# midicontroller.net
KiCad netlist of a schematic drawn in EAGLE
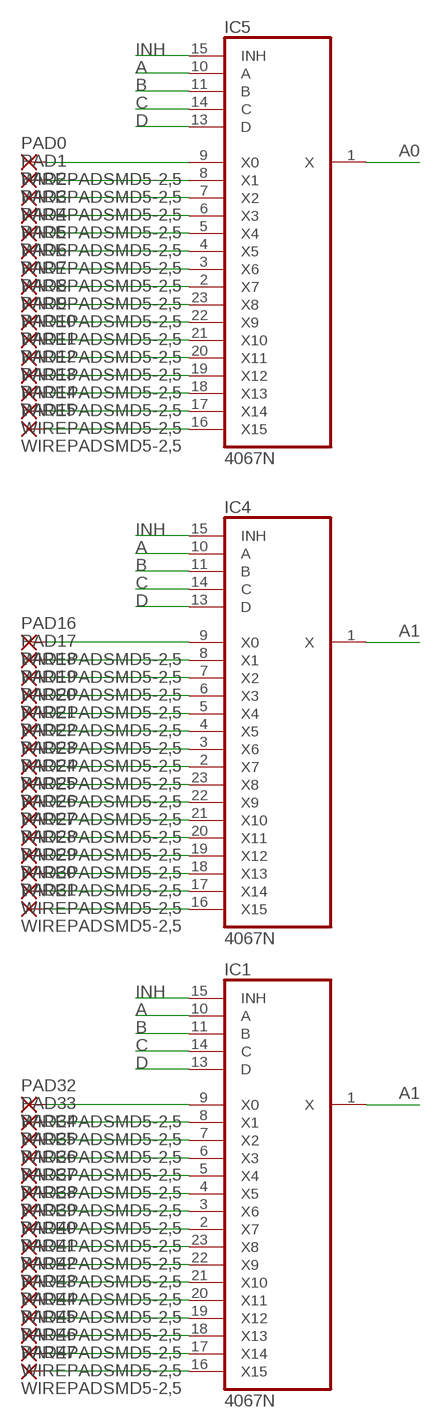
[diagram p0: schematic, sheet 1]

(export (version "E")
  (design (tool "Eeschema 10.0.6"))
  (components
    (comp (ref "IC1")
      (value "4067N")
      (footprint "eagle-import:DIL24-6")
      (libsource (lib "eagle-import") (part "4067N"))
    )
    (comp (ref "IC4")
      (value "4067N")
      (footprint "eagle-import:DIL24-6")
      (libsource (lib "eagle-import") (part "4067N"))
    )
    (comp (ref "IC5")
      (value "4067N")
      (footprint "eagle-import:DIL24-6")
      (libsource (lib "eagle-import") (part "4067N"))
    )
    (comp (ref "PAD0")
      (value "WIREPADSMD5-2,5")
      (footprint "eagle-import:5-2,5")
      (libsource (lib "eagle-import") (part "WIREPADSMD5-2,5"))
    )
    (comp (ref "PAD1")
      (value "WIREPADSMD5-2,5")
      (footprint "eagle-import:5-2,5")
      (libsource (lib "eagle-import") (part "WIREPADSMD5-2,5"))
    )
    (comp (ref "PAD2")
      (value "WIREPADSMD5-2,5")
      (footprint "eagle-import:5-2,5")
      (libsource (lib "eagle-import") (part "WIREPADSMD5-2,5"))
    )
    (comp (ref "PAD3")
      (value "WIREPADSMD5-2,5")
      (footprint "eagle-import:5-2,5")
      (libsource (lib "eagle-import") (part "WIREPADSMD5-2,5"))
    )
    (comp (ref "PAD4")
      (value "WIREPADSMD5-2,5")
      (footprint "eagle-import:5-2,5")
      (libsource (lib "eagle-import") (part "WIREPADSMD5-2,5"))
    )
    (comp (ref "PAD5")
      (value "WIREPADSMD5-2,5")
      (footprint "eagle-import:5-2,5")
      (libsource (lib "eagle-import") (part "WIREPADSMD5-2,5"))
    )
    (comp (ref "PAD6")
      (value "WIREPADSMD5-2,5")
      (footprint "eagle-import:5-2,5")
      (libsource (lib "eagle-import") (part "WIREPADSMD5-2,5"))
    )
    (comp (ref "PAD7")
      (value "WIREPADSMD5-2,5")
      (footprint "eagle-import:5-2,5")
      (libsource (lib "eagle-import") (part "WIREPADSMD5-2,5"))
    )
    (comp (ref "PAD8")
      (value "WIREPADSMD5-2,5")
      (footprint "eagle-import:5-2,5")
      (libsource (lib "eagle-import") (part "WIREPADSMD5-2,5"))
    )
    (comp (ref "PAD9")
      (value "WIREPADSMD5-2,5")
      (footprint "eagle-import:5-2,5")
      (libsource (lib "eagle-import") (part "WIREPADSMD5-2,5"))
    )
    (comp (ref "PAD10")
      (value "WIREPADSMD5-2,5")
      (footprint "eagle-import:5-2,5")
      (libsource (lib "eagle-import") (part "WIREPADSMD5-2,5"))
    )
    (comp (ref "PAD11")
      (value "WIREPADSMD5-2,5")
      (footprint "eagle-import:5-2,5")
      (libsource (lib "eagle-import") (part "WIREPADSMD5-2,5"))
    )
    (comp (ref "PAD12")
      (value "WIREPADSMD5-2,5")
      (footprint "eagle-import:5-2,5")
      (libsource (lib "eagle-import") (part "WIREPADSMD5-2,5"))
    )
    (comp (ref "PAD13")
      (value "WIREPADSMD5-2,5")
      (footprint "eagle-import:5-2,5")
      (libsource (lib "eagle-import") (part "WIREPADSMD5-2,5"))
    )
    (comp (ref "PAD14")
      (value "WIREPADSMD5-2,5")
      (footprint "eagle-import:5-2,5")
      (libsource (lib "eagle-import") (part "WIREPADSMD5-2,5"))
    )
    (comp (ref "PAD15")
      (value "WIREPADSMD5-2,5")
      (footprint "eagle-import:5-2,5")
      (libsource (lib "eagle-import") (part "WIREPADSMD5-2,5"))
    )
    (comp (ref "PAD16")
      (value "WIREPADSMD5-2,5")
      (footprint "eagle-import:5-2,5")
      (libsource (lib "eagle-import") (part "WIREPADSMD5-2,5"))
    )
    (comp (ref "PAD17")
      (value "WIREPADSMD5-2,5")
      (footprint "eagle-import:5-2,5")
      (libsource (lib "eagle-import") (part "WIREPADSMD5-2,5"))
    )
    (comp (ref "PAD18")
      (value "WIREPADSMD5-2,5")
      (footprint "eagle-import:5-2,5")
      (libsource (lib "eagle-import") (part "WIREPADSMD5-2,5"))
    )
    (comp (ref "PAD19")
      (value "WIREPADSMD5-2,5")
      (footprint "eagle-import:5-2,5")
      (libsource (lib "eagle-import") (part "WIREPADSMD5-2,5"))
    )
    (comp (ref "PAD20")
      (value "WIREPADSMD5-2,5")
      (footprint "eagle-import:5-2,5")
      (libsource (lib "eagle-import") (part "WIREPADSMD5-2,5"))
    )
    (comp (ref "PAD21")
      (value "WIREPADSMD5-2,5")
      (footprint "eagle-import:5-2,5")
      (libsource (lib "eagle-import") (part "WIREPADSMD5-2,5"))
    )
    (comp (ref "PAD22")
      (value "WIREPADSMD5-2,5")
      (footprint "eagle-import:5-2,5")
      (libsource (lib "eagle-import") (part "WIREPADSMD5-2,5"))
    )
    (comp (ref "PAD23")
      (value "WIREPADSMD5-2,5")
      (footprint "eagle-import:5-2,5")
      (libsource (lib "eagle-import") (part "WIREPADSMD5-2,5"))
    )
    (comp (ref "PAD24")
      (value "WIREPADSMD5-2,5")
      (footprint "eagle-import:5-2,5")
      (libsource (lib "eagle-import") (part "WIREPADSMD5-2,5"))
    )
    (comp (ref "PAD25")
      (value "WIREPADSMD5-2,5")
      (footprint "eagle-import:5-2,5")
      (libsource (lib "eagle-import") (part "WIREPADSMD5-2,5"))
    )
    (comp (ref "PAD26")
      (value "WIREPADSMD5-2,5")
      (footprint "eagle-import:5-2,5")
      (libsource (lib "eagle-import") (part "WIREPADSMD5-2,5"))
    )
    (comp (ref "PAD27")
      (value "WIREPADSMD5-2,5")
      (footprint "eagle-import:5-2,5")
      (libsource (lib "eagle-import") (part "WIREPADSMD5-2,5"))
    )
    (comp (ref "PAD28")
      (value "WIREPADSMD5-2,5")
      (footprint "eagle-import:5-2,5")
      (libsource (lib "eagle-import") (part "WIREPADSMD5-2,5"))
    )
    (comp (ref "PAD29")
      (value "WIREPADSMD5-2,5")
      (footprint "eagle-import:5-2,5")
      (libsource (lib "eagle-import") (part "WIREPADSMD5-2,5"))
    )
    (comp (ref "PAD30")
      (value "WIREPADSMD5-2,5")
      (footprint "eagle-import:5-2,5")
      (libsource (lib "eagle-import") (part "WIREPADSMD5-2,5"))
    )
    (comp (ref "PAD31")
      (value "WIREPADSMD5-2,5")
      (footprint "eagle-import:5-2,5")
      (libsource (lib "eagle-import") (part "WIREPADSMD5-2,5"))
    )
    (comp (ref "PAD32")
      (value "WIREPADSMD5-2,5")
      (footprint "eagle-import:5-2,5")
      (libsource (lib "eagle-import") (part "WIREPADSMD5-2,5"))
    )
    (comp (ref "PAD33")
      (value "WIREPADSMD5-2,5")
      (footprint "eagle-import:5-2,5")
      (libsource (lib "eagle-import") (part "WIREPADSMD5-2,5"))
    )
    (comp (ref "PAD34")
      (value "WIREPADSMD5-2,5")
      (footprint "eagle-import:5-2,5")
      (libsource (lib "eagle-import") (part "WIREPADSMD5-2,5"))
    )
    (comp (ref "PAD35")
      (value "WIREPADSMD5-2,5")
      (footprint "eagle-import:5-2,5")
      (libsource (lib "eagle-import") (part "WIREPADSMD5-2,5"))
    )
    (comp (ref "PAD36")
      (value "WIREPADSMD5-2,5")
      (footprint "eagle-import:5-2,5")
      (libsource (lib "eagle-import") (part "WIREPADSMD5-2,5"))
    )
    (comp (ref "PAD37")
      (value "WIREPADSMD5-2,5")
      (footprint "eagle-import:5-2,5")
      (libsource (lib "eagle-import") (part "WIREPADSMD5-2,5"))
    )
    (comp (ref "PAD38")
      (value "WIREPADSMD5-2,5")
      (footprint "eagle-import:5-2,5")
      (libsource (lib "eagle-import") (part "WIREPADSMD5-2,5"))
    )
    (comp (ref "PAD39")
      (value "WIREPADSMD5-2,5")
      (footprint "eagle-import:5-2,5")
      (libsource (lib "eagle-import") (part "WIREPADSMD5-2,5"))
    )
    (comp (ref "PAD40")
      (value "WIREPADSMD5-2,5")
      (footprint "eagle-import:5-2,5")
      (libsource (lib "eagle-import") (part "WIREPADSMD5-2,5"))
    )
    (comp (ref "PAD41")
      (value "WIREPADSMD5-2,5")
      (footprint "eagle-import:5-2,5")
      (libsource (lib "eagle-import") (part "WIREPADSMD5-2,5"))
    )
    (comp (ref "PAD42")
      (value "WIREPADSMD5-2,5")
      (footprint "eagle-import:5-2,5")
      (libsource (lib "eagle-import") (part "WIREPADSMD5-2,5"))
    )
    (comp (ref "PAD43")
      (value "WIREPADSMD5-2,5")
      (footprint "eagle-import:5-2,5")
      (libsource (lib "eagle-import") (part "WIREPADSMD5-2,5"))
    )
    (comp (ref "PAD44")
      (value "WIREPADSMD5-2,5")
      (footprint "eagle-import:5-2,5")
      (libsource (lib "eagle-import") (part "WIREPADSMD5-2,5"))
    )
    (comp (ref "PAD45")
      (value "WIREPADSMD5-2,5")
      (footprint "eagle-import:5-2,5")
      (libsource (lib "eagle-import") (part "WIREPADSMD5-2,5"))
    )
    (comp (ref "PAD46")
      (value "WIREPADSMD5-2,5")
      (footprint "eagle-import:5-2,5")
      (libsource (lib "eagle-import") (part "WIREPADSMD5-2,5"))
    )
    (comp (ref "PAD47")
      (value "WIREPADSMD5-2,5")
      (footprint "eagle-import:5-2,5")
      (libsource (lib "eagle-import") (part "WIREPADSMD5-2,5"))
    )
  )
  (nets
    (net (code "1") (name "/A") (class "Default")
      (node (ref "IC1") (pin "10") (pinfunction "A_10") (pintype "input"))
      (node (ref "IC4") (pin "10") (pinfunction "A_10") (pintype "input"))
      (node (ref "IC5") (pin "10") (pinfunction "A_10") (pintype "input"))
    )
    (net (code "2") (name "/A0") (class "Default")
      (node (ref "IC5") (pin "1") (pinfunction "X_1") (pintype "output"))
    )
    (net (code "3") (name "/A1") (class "Default")
      (node (ref "IC1") (pin "1") (pinfunction "X_1") (pintype "output"))
      (node (ref "IC4") (pin "1") (pinfunction "X_1") (pintype "output"))
    )
    (net (code "4") (name "/B") (class "Default")
      (node (ref "IC1") (pin "11") (pinfunction "B_11") (pintype "input"))
      (node (ref "IC4") (pin "11") (pinfunction "B_11") (pintype "input"))
      (node (ref "IC5") (pin "11") (pinfunction "B_11") (pintype "input"))
    )
    (net (code "5") (name "/C") (class "Default")
      (node (ref "IC1") (pin "14") (pinfunction "C_14") (pintype "input"))
      (node (ref "IC4") (pin "14") (pinfunction "C_14") (pintype "input"))
      (node (ref "IC5") (pin "14") (pinfunction "C_14") (pintype "input"))
    )
    (net (code "6") (name "/D") (class "Default")
      (node (ref "IC1") (pin "13") (pinfunction "D_13") (pintype "input"))
      (node (ref "IC4") (pin "13") (pinfunction "D_13") (pintype "input"))
      (node (ref "IC5") (pin "13") (pinfunction "D_13") (pintype "input"))
    )
    (net (code "7") (name "/INH") (class "Default")
      (node (ref "IC1") (pin "15") (pinfunction "INH_15") (pintype "input"))
      (node (ref "IC4") (pin "15") (pinfunction "INH_15") (pintype "input"))
      (node (ref "IC5") (pin "15") (pinfunction "INH_15") (pintype "input"))
    )
    (net (code "8") (name "Net-(IC1A-X0)") (class "Default")
      (node (ref "IC1") (pin "9") (pinfunction "X0_9") (pintype "input"))
      (node (ref "PAD32") (pin "1") (pinfunction "P_1") (pintype "passive"))
    )
    (net (code "9") (name "Net-(IC1A-X1)") (class "Default")
      (node (ref "IC1") (pin "8") (pinfunction "X1_8") (pintype "input"))
      (node (ref "PAD33") (pin "1") (pinfunction "P_1") (pintype "passive"))
    )
    (net (code "10") (name "Net-(IC1A-X2)") (class "Default")
      (node (ref "IC1") (pin "7") (pinfunction "X2_7") (pintype "input"))
      (node (ref "PAD34") (pin "1") (pinfunction "P_1") (pintype "passive"))
    )
    (net (code "11") (name "Net-(IC1A-X3)") (class "Default")
      (node (ref "IC1") (pin "6") (pinfunction "X3_6") (pintype "input"))
      (node (ref "PAD35") (pin "1") (pinfunction "P_1") (pintype "passive"))
    )
    (net (code "12") (name "Net-(IC1A-X4)") (class "Default")
      (node (ref "IC1") (pin "5") (pinfunction "X4_5") (pintype "input"))
      (node (ref "PAD36") (pin "1") (pinfunction "P_1") (pintype "passive"))
    )
    (net (code "13") (name "Net-(IC1A-X5)") (class "Default")
      (node (ref "IC1") (pin "4") (pinfunction "X5_4") (pintype "input"))
      (node (ref "PAD37") (pin "1") (pinfunction "P_1") (pintype "passive"))
    )
    (net (code "14") (name "Net-(IC1A-X6)") (class "Default")
      (node (ref "IC1") (pin "3") (pinfunction "X6_3") (pintype "input"))
      (node (ref "PAD38") (pin "1") (pinfunction "P_1") (pintype "passive"))
    )
    (net (code "15") (name "Net-(IC1A-X7)") (class "Default")
      (node (ref "IC1") (pin "2") (pinfunction "X7_2") (pintype "input"))
      (node (ref "PAD39") (pin "1") (pinfunction "P_1") (pintype "passive"))
    )
    (net (code "16") (name "Net-(IC1A-X8)") (class "Default")
      (node (ref "IC1") (pin "23") (pinfunction "X8_23") (pintype "input"))
      (node (ref "PAD40") (pin "1") (pinfunction "P_1") (pintype "passive"))
    )
    (net (code "17") (name "Net-(IC1A-X9)") (class "Default")
      (node (ref "IC1") (pin "22") (pinfunction "X9_22") (pintype "input"))
      (node (ref "PAD41") (pin "1") (pinfunction "P_1") (pintype "passive"))
    )
    (net (code "18") (name "Net-(IC1A-X10)") (class "Default")
      (node (ref "IC1") (pin "21") (pinfunction "X10_21") (pintype "input"))
      (node (ref "PAD42") (pin "1") (pinfunction "P_1") (pintype "passive"))
    )
    (net (code "19") (name "Net-(IC1A-X11)") (class "Default")
      (node (ref "IC1") (pin "20") (pinfunction "X11_20") (pintype "input"))
      (node (ref "PAD43") (pin "1") (pinfunction "P_1") (pintype "passive"))
    )
    (net (code "20") (name "Net-(IC1A-X12)") (class "Default")
      (node (ref "IC1") (pin "19") (pinfunction "X12_19") (pintype "input"))
      (node (ref "PAD44") (pin "1") (pinfunction "P_1") (pintype "passive"))
    )
    (net (code "21") (name "Net-(IC1A-X13)") (class "Default")
      (node (ref "IC1") (pin "18") (pinfunction "X13_18") (pintype "input"))
      (node (ref "PAD45") (pin "1") (pinfunction "P_1") (pintype "passive"))
    )
    (net (code "22") (name "Net-(IC1A-X14)") (class "Default")
      (node (ref "IC1") (pin "17") (pinfunction "X14_17") (pintype "input"))
      (node (ref "PAD46") (pin "1") (pinfunction "P_1") (pintype "passive"))
    )
    (net (code "23") (name "Net-(IC1A-X15)") (class "Default")
      (node (ref "IC1") (pin "16") (pinfunction "X15_16") (pintype "input"))
      (node (ref "PAD47") (pin "1") (pinfunction "P_1") (pintype "passive"))
    )
    (net (code "24") (name "Net-(IC4A-X0)") (class "Default")
      (node (ref "IC4") (pin "9") (pinfunction "X0_9") (pintype "input"))
      (node (ref "PAD16") (pin "1") (pinfunction "P_1") (pintype "passive"))
    )
    (net (code "25") (name "Net-(IC4A-X1)") (class "Default")
      (node (ref "IC4") (pin "8") (pinfunction "X1_8") (pintype "input"))
      (node (ref "PAD17") (pin "1") (pinfunction "P_1") (pintype "passive"))
    )
    (net (code "26") (name "Net-(IC4A-X2)") (class "Default")
      (node (ref "IC4") (pin "7") (pinfunction "X2_7") (pintype "input"))
      (node (ref "PAD18") (pin "1") (pinfunction "P_1") (pintype "passive"))
    )
    (net (code "27") (name "Net-(IC4A-X3)") (class "Default")
      (node (ref "IC4") (pin "6") (pinfunction "X3_6") (pintype "input"))
      (node (ref "PAD19") (pin "1") (pinfunction "P_1") (pintype "passive"))
    )
    (net (code "28") (name "Net-(IC4A-X4)") (class "Default")
      (node (ref "IC4") (pin "5") (pinfunction "X4_5") (pintype "input"))
      (node (ref "PAD20") (pin "1") (pinfunction "P_1") (pintype "passive"))
    )
    (net (code "29") (name "Net-(IC4A-X5)") (class "Default")
      (node (ref "IC4") (pin "4") (pinfunction "X5_4") (pintype "input"))
      (node (ref "PAD21") (pin "1") (pinfunction "P_1") (pintype "passive"))
    )
    (net (code "30") (name "Net-(IC4A-X6)") (class "Default")
      (node (ref "IC4") (pin "3") (pinfunction "X6_3") (pintype "input"))
      (node (ref "PAD22") (pin "1") (pinfunction "P_1") (pintype "passive"))
    )
    (net (code "31") (name "Net-(IC4A-X7)") (class "Default")
      (node (ref "IC4") (pin "2") (pinfunction "X7_2") (pintype "input"))
      (node (ref "PAD23") (pin "1") (pinfunction "P_1") (pintype "passive"))
    )
    (net (code "32") (name "Net-(IC4A-X8)") (class "Default")
      (node (ref "IC4") (pin "23") (pinfunction "X8_23") (pintype "input"))
      (node (ref "PAD24") (pin "1") (pinfunction "P_1") (pintype "passive"))
    )
    (net (code "33") (name "Net-(IC4A-X9)") (class "Default")
      (node (ref "IC4") (pin "22") (pinfunction "X9_22") (pintype "input"))
      (node (ref "PAD25") (pin "1") (pinfunction "P_1") (pintype "passive"))
    )
    (net (code "34") (name "Net-(IC4A-X10)") (class "Default")
      (node (ref "IC4") (pin "21") (pinfunction "X10_21") (pintype "input"))
      (node (ref "PAD26") (pin "1") (pinfunction "P_1") (pintype "passive"))
    )
    (net (code "35") (name "Net-(IC4A-X11)") (class "Default")
      (node (ref "IC4") (pin "20") (pinfunction "X11_20") (pintype "input"))
      (node (ref "PAD27") (pin "1") (pinfunction "P_1") (pintype "passive"))
    )
    (net (code "36") (name "Net-(IC4A-X12)") (class "Default")
      (node (ref "IC4") (pin "19") (pinfunction "X12_19") (pintype "input"))
      (node (ref "PAD28") (pin "1") (pinfunction "P_1") (pintype "passive"))
    )
    (net (code "37") (name "Net-(IC4A-X13)") (class "Default")
      (node (ref "IC4") (pin "18") (pinfunction "X13_18") (pintype "input"))
      (node (ref "PAD29") (pin "1") (pinfunction "P_1") (pintype "passive"))
    )
    (net (code "38") (name "Net-(IC4A-X14)") (class "Default")
      (node (ref "IC4") (pin "17") (pinfunction "X14_17") (pintype "input"))
      (node (ref "PAD30") (pin "1") (pinfunction "P_1") (pintype "passive"))
    )
    (net (code "39") (name "Net-(IC4A-X15)") (class "Default")
      (node (ref "IC4") (pin "16") (pinfunction "X15_16") (pintype "input"))
      (node (ref "PAD31") (pin "1") (pinfunction "P_1") (pintype "passive"))
    )
    (net (code "40") (name "Net-(IC5A-X0)") (class "Default")
      (node (ref "IC5") (pin "9") (pinfunction "X0_9") (pintype "input"))
      (node (ref "PAD0") (pin "1") (pinfunction "P_1") (pintype "passive"))
    )
    (net (code "41") (name "Net-(IC5A-X1)") (class "Default")
      (node (ref "IC5") (pin "8") (pinfunction "X1_8") (pintype "input"))
      (node (ref "PAD1") (pin "1") (pinfunction "P_1") (pintype "passive"))
    )
    (net (code "42") (name "Net-(IC5A-X2)") (class "Default")
      (node (ref "IC5") (pin "7") (pinfunction "X2_7") (pintype "input"))
      (node (ref "PAD2") (pin "1") (pinfunction "P_1") (pintype "passive"))
    )
    (net (code "43") (name "Net-(IC5A-X3)") (class "Default")
      (node (ref "IC5") (pin "6") (pinfunction "X3_6") (pintype "input"))
      (node (ref "PAD3") (pin "1") (pinfunction "P_1") (pintype "passive"))
    )
    (net (code "44") (name "Net-(IC5A-X4)") (class "Default")
      (node (ref "IC5") (pin "5") (pinfunction "X4_5") (pintype "input"))
      (node (ref "PAD4") (pin "1") (pinfunction "P_1") (pintype "passive"))
    )
    (net (code "45") (name "Net-(IC5A-X5)") (class "Default")
      (node (ref "IC5") (pin "4") (pinfunction "X5_4") (pintype "input"))
      (node (ref "PAD5") (pin "1") (pinfunction "P_1") (pintype "passive"))
    )
    (net (code "46") (name "Net-(IC5A-X6)") (class "Default")
      (node (ref "IC5") (pin "3") (pinfunction "X6_3") (pintype "input"))
      (node (ref "PAD6") (pin "1") (pinfunction "P_1") (pintype "passive"))
    )
    (net (code "47") (name "Net-(IC5A-X7)") (class "Default")
      (node (ref "IC5") (pin "2") (pinfunction "X7_2") (pintype "input"))
      (node (ref "PAD7") (pin "1") (pinfunction "P_1") (pintype "passive"))
    )
    (net (code "48") (name "Net-(IC5A-X8)") (class "Default")
      (node (ref "IC5") (pin "23") (pinfunction "X8_23") (pintype "input"))
      (node (ref "PAD8") (pin "1") (pinfunction "P_1") (pintype "passive"))
    )
    (net (code "49") (name "Net-(IC5A-X9)") (class "Default")
      (node (ref "IC5") (pin "22") (pinfunction "X9_22") (pintype "input"))
      (node (ref "PAD9") (pin "1") (pinfunction "P_1") (pintype "passive"))
    )
    (net (code "50") (name "Net-(IC5A-X10)") (class "Default")
      (node (ref "IC5") (pin "21") (pinfunction "X10_21") (pintype "input"))
      (node (ref "PAD10") (pin "1") (pinfunction "P_1") (pintype "passive"))
    )
    (net (code "51") (name "Net-(IC5A-X11)") (class "Default")
      (node (ref "IC5") (pin "20") (pinfunction "X11_20") (pintype "input"))
      (node (ref "PAD11") (pin "1") (pinfunction "P_1") (pintype "passive"))
    )
    (net (code "52") (name "Net-(IC5A-X12)") (class "Default")
      (node (ref "IC5") (pin "19") (pinfunction "X12_19") (pintype "input"))
      (node (ref "PAD12") (pin "1") (pinfunction "P_1") (pintype "passive"))
    )
    (net (code "53") (name "Net-(IC5A-X13)") (class "Default")
      (node (ref "IC5") (pin "18") (pinfunction "X13_18") (pintype "input"))
      (node (ref "PAD13") (pin "1") (pinfunction "P_1") (pintype "passive"))
    )
    (net (code "54") (name "Net-(IC5A-X14)") (class "Default")
      (node (ref "IC5") (pin "17") (pinfunction "X14_17") (pintype "input"))
      (node (ref "PAD14") (pin "1") (pinfunction "P_1") (pintype "passive"))
    )
    (net (code "55") (name "Net-(IC5A-X15)") (class "Default")
      (node (ref "IC5") (pin "16") (pinfunction "X15_16") (pintype "input"))
      (node (ref "PAD15") (pin "1") (pinfunction "P_1") (pintype "passive"))
    )
  )
)
